# throughHoleAdapter.net
KiCad netlist of a schematic drawn in EAGLE
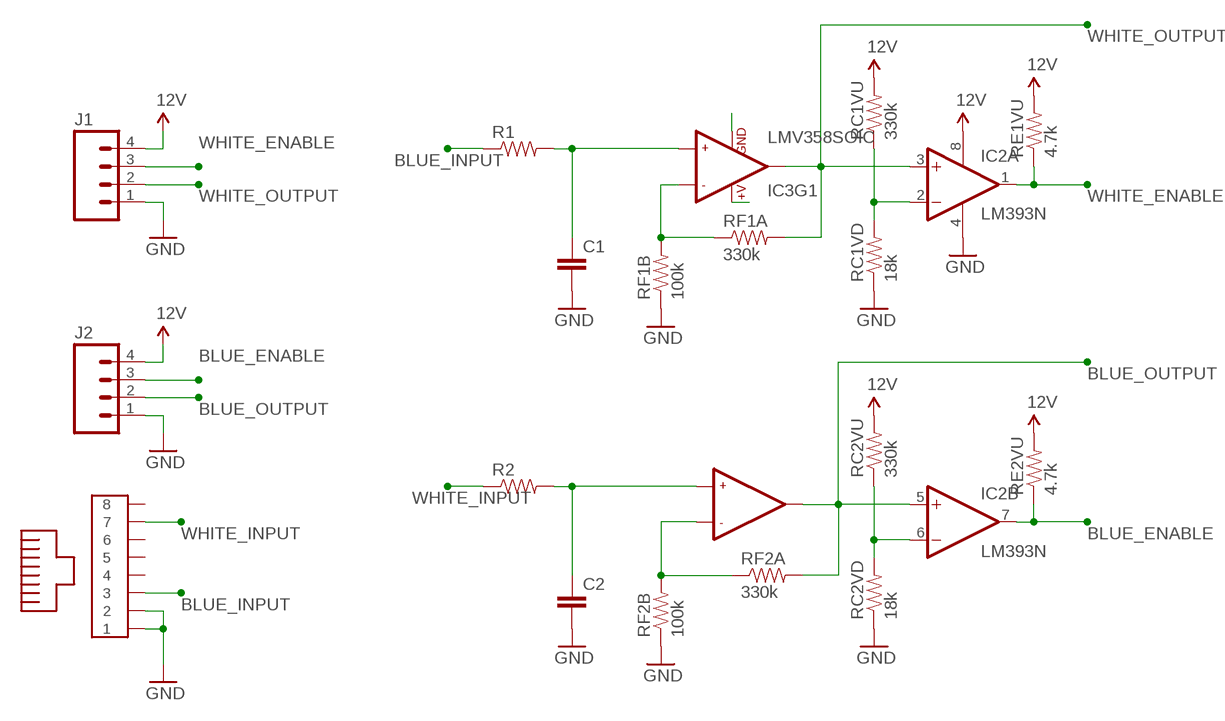
[diagram p0: schematic, sheet 1]

(export (version "E")
  (design (tool "Eeschema 10.0.6"))
  (components
    (comp (ref "C1")
      (value "CAPKIT")
      (footprint "eagle-import:CAP-PTH-SMALL-KIT")
      (libsource (lib "eagle-import") (part "CAPKIT"))
    )
    (comp (ref "C2")
      (value "CAPKIT")
      (footprint "eagle-import:CAP-PTH-SMALL-KIT")
      (libsource (lib "eagle-import") (part "CAPKIT"))
    )
    (comp (ref "IC2")
      (value "LM393N")
      (footprint "eagle-import:DIL08")
      (libsource (lib "eagle-import") (part "LM393N"))
    )
    (comp (ref "IC3")
      (value "LMV358SOIC")
      (footprint "eagle-import:SO08")
      (libsource (lib "eagle-import") (part "LMV358SOIC"))
    )
    (comp (ref "J1")
      (value "M04LONGPADS")
      (footprint "eagle-import:1X04_LONGPADS")
      (libsource (lib "eagle-import") (part "M04LONGPADS"))
    )
    (comp (ref "J2")
      (value "M04LONGPADS")
      (footprint "eagle-import:1X04_LONGPADS")
      (libsource (lib "eagle-import") (part "M04LONGPADS"))
    )
    (comp (ref "R1")
      (value "RESISTOR1206")
      (footprint "eagle-import:1206")
      (libsource (lib "eagle-import") (part "RESISTOR1206"))
    )
    (comp (ref "R2")
      (value "RESISTOR1206")
      (footprint "eagle-import:1206")
      (libsource (lib "eagle-import") (part "RESISTOR1206"))
    )
    (comp (ref "RC1VD")
      (value "18k")
      (footprint "eagle-import:1206")
      (libsource (lib "eagle-import") (part "RESISTOR1206"))
    )
    (comp (ref "RC1VU")
      (value "330k")
      (footprint "eagle-import:1206")
      (libsource (lib "eagle-import") (part "RESISTOR1206"))
    )
    (comp (ref "RC2VD")
      (value "18k")
      (footprint "eagle-import:1206")
      (libsource (lib "eagle-import") (part "RESISTOR1206"))
    )
    (comp (ref "RC2VU")
      (value "330k")
      (footprint "eagle-import:1206")
      (libsource (lib "eagle-import") (part "RESISTOR1206"))
    )
    (comp (ref "RE1VU")
      (value "4.7k")
      (footprint "eagle-import:1206")
      (libsource (lib "eagle-import") (part "RESISTOR1206"))
    )
    (comp (ref "RE2VU")
      (value "4.7k")
      (footprint "eagle-import:1206")
      (libsource (lib "eagle-import") (part "RESISTOR1206"))
    )
    (comp (ref "RF1A")
      (value "330k")
      (footprint "eagle-import:1206")
      (libsource (lib "eagle-import") (part "RESISTOR1206"))
    )
    (comp (ref "RF1B")
      (value "100k")
      (footprint "eagle-import:1206")
      (libsource (lib "eagle-import") (part "RESISTOR1206"))
    )
    (comp (ref "RF2A")
      (value "330k")
      (footprint "eagle-import:1206")
      (libsource (lib "eagle-import") (part "RESISTOR1206"))
    )
    (comp (ref "RF2B")
      (value "100k")
      (footprint "eagle-import:1206")
      (libsource (lib "eagle-import") (part "RESISTOR1206"))
    )
    (comp (ref "U$1")
      (value "MOLEX-RJ45-SMT")
      (footprint "eagle-import:MOLEX-RJ45-SMT")
      (libsource (lib "eagle-import") (part "MOLEX-RJ45-SMT"))
    )
  )
  (nets
    (net (code "1") (name "/BLUE_ENABLE") (class "Default")
      (node (ref "IC2") (pin "7") (pinfunction "OUT_7") (pintype "output"))
      (node (ref "J2") (pin "3") (pinfunction "3_3") (pintype "passive"))
      (node (ref "RE2VU") (pin "1") (pinfunction "1_1") (pintype "passive"))
    )
    (net (code "2") (name "/BLUE_INPUT") (class "Default")
      (node (ref "R1") (pin "1") (pinfunction "1_1") (pintype "passive"))
      (node (ref "U$1") (pin "3") (pinfunction "3_3") (pintype "bidirectional"))
    )
    (net (code "3") (name "/BLUE_OUTPUT") (class "Default")
      (node (ref "IC2") (pin "5") (pinfunction "+IN_5") (pintype "input"))
      (node (ref "IC3") (pin "7") (pinfunction "OUT2_7") (pintype "output"))
      (node (ref "J2") (pin "2") (pinfunction "2_2") (pintype "passive"))
      (node (ref "RF2A") (pin "2") (pinfunction "2_2") (pintype "passive"))
    )
    (net (code "4") (name "/WHITE_ENABLE") (class "Default")
      (node (ref "IC2") (pin "1") (pinfunction "OUT_1") (pintype "output"))
      (node (ref "J1") (pin "3") (pinfunction "3_3") (pintype "passive"))
      (node (ref "RE1VU") (pin "1") (pinfunction "1_1") (pintype "passive"))
    )
    (net (code "5") (name "/WHITE_INPUT") (class "Default")
      (node (ref "R2") (pin "1") (pinfunction "1_1") (pintype "passive"))
      (node (ref "U$1") (pin "7") (pinfunction "7_7") (pintype "bidirectional"))
    )
    (net (code "6") (name "/WHITE_OUTPUT") (class "Default")
      (node (ref "IC2") (pin "3") (pinfunction "+IN_3") (pintype "input"))
      (node (ref "IC3") (pin "1") (pinfunction "OUT1_1") (pintype "output"))
      (node (ref "J1") (pin "2") (pinfunction "2_2") (pintype "passive"))
      (node (ref "RF1A") (pin "2") (pinfunction "2_2") (pintype "passive"))
    )
    (net (code "7") (name "12V") (class "Default")
      (node (ref "IC2") (pin "8") (pinfunction "V+_8") (pintype "power_in"))
      (node (ref "IC3") (pin "8") (pinfunction "+V_8") (pintype "power_in"))
      (node (ref "J1") (pin "4") (pinfunction "4_4") (pintype "passive"))
      (node (ref "J2") (pin "4") (pinfunction "4_4") (pintype "passive"))
      (node (ref "RC1VU") (pin "2") (pinfunction "2_2") (pintype "passive"))
      (node (ref "RC2VU") (pin "2") (pinfunction "2_2") (pintype "passive"))
      (node (ref "RE1VU") (pin "2") (pinfunction "2_2") (pintype "passive"))
      (node (ref "RE2VU") (pin "2") (pinfunction "2_2") (pintype "passive"))
    )
    (net (code "8") (name "GND") (class "Default")
      (node (ref "C1") (pin "2") (pinfunction "2_2") (pintype "passive"))
      (node (ref "C2") (pin "2") (pinfunction "2_2") (pintype "passive"))
      (node (ref "IC2") (pin "4") (pinfunction "V-_4") (pintype "power_in"))
      (node (ref "IC3") (pin "4") (pinfunction "GND_4") (pintype "power_in"))
      (node (ref "J1") (pin "1") (pinfunction "1_1") (pintype "passive"))
      (node (ref "J2") (pin "1") (pinfunction "1_1") (pintype "passive"))
      (node (ref "RC1VD") (pin "1") (pinfunction "1_1") (pintype "passive"))
      (node (ref "RC2VD") (pin "1") (pinfunction "1_1") (pintype "passive"))
      (node (ref "RF1B") (pin "1") (pinfunction "1_1") (pintype "passive"))
      (node (ref "RF2B") (pin "1") (pinfunction "1_1") (pintype "passive"))
      (node (ref "U$1") (pin "1") (pinfunction "1_1") (pintype "bidirectional"))
      (node (ref "U$1") (pin "2") (pinfunction "2_2") (pintype "bidirectional"))
    )
    (net (code "9") (name "Net-(IC2A--IN)") (class "Default")
      (node (ref "IC2") (pin "2") (pinfunction "-IN_2") (pintype "input"))
      (node (ref "RC1VD") (pin "2") (pinfunction "2_2") (pintype "passive"))
      (node (ref "RC1VU") (pin "1") (pinfunction "1_1") (pintype "passive"))
    )
    (net (code "10") (name "Net-(IC2B--IN)") (class "Default")
      (node (ref "IC2") (pin "6") (pinfunction "-IN_6") (pintype "input"))
      (node (ref "RC2VD") (pin "2") (pinfunction "2_2") (pintype "passive"))
      (node (ref "RC2VU") (pin "1") (pinfunction "1_1") (pintype "passive"))
    )
    (net (code "11") (name "Net-(IC3A-+IN1)") (class "Default")
      (node (ref "C1") (pin "1") (pinfunction "1_1") (pintype "passive"))
      (node (ref "IC3") (pin "3") (pinfunction "+IN1_3") (pintype "input"))
      (node (ref "R1") (pin "2") (pinfunction "2_2") (pintype "passive"))
    )
    (net (code "12") (name "Net-(IC3A--IN1)") (class "Default")
      (node (ref "IC3") (pin "2") (pinfunction "-IN1_2") (pintype "input"))
      (node (ref "RF1A") (pin "1") (pinfunction "1_1") (pintype "passive"))
      (node (ref "RF1B") (pin "2") (pinfunction "2_2") (pintype "passive"))
    )
    (net (code "13") (name "Net-(IC3B-+IN2)") (class "Default")
      (node (ref "C2") (pin "1") (pinfunction "1_1") (pintype "passive"))
      (node (ref "IC3") (pin "5") (pinfunction "+IN2_5") (pintype "input"))
      (node (ref "R2") (pin "2") (pinfunction "2_2") (pintype "passive"))
    )
    (net (code "14") (name "Net-(IC3B--IN2)") (class "Default")
      (node (ref "IC3") (pin "6") (pinfunction "-IN2_6") (pintype "input"))
      (node (ref "RF2A") (pin "1") (pinfunction "1_1") (pintype "passive"))
      (node (ref "RF2B") (pin "2") (pinfunction "2_2") (pintype "passive"))
    )
    (net (code "15") (name "unconnected-(U$1-Pad4)") (class "Default")
      (node (ref "U$1") (pin "4") (pinfunction "4_4") (pintype "bidirectional"))
    )
    (net (code "16") (name "unconnected-(U$1-Pad5)") (class "Default")
      (node (ref "U$1") (pin "5") (pinfunction "5_5") (pintype "bidirectional"))
    )
    (net (code "17") (name "unconnected-(U$1-Pad6)") (class "Default")
      (node (ref "U$1") (pin "6") (pinfunction "6_6") (pintype "bidirectional"))
    )
    (net (code "18") (name "unconnected-(U$1-Pad8)") (class "Default")
      (node (ref "U$1") (pin "8") (pinfunction "8_8") (pintype "bidirectional"))
    )
  )
)
